# 3-CAN.net
KiCad netlist of a schematic drawn in Altium Designer
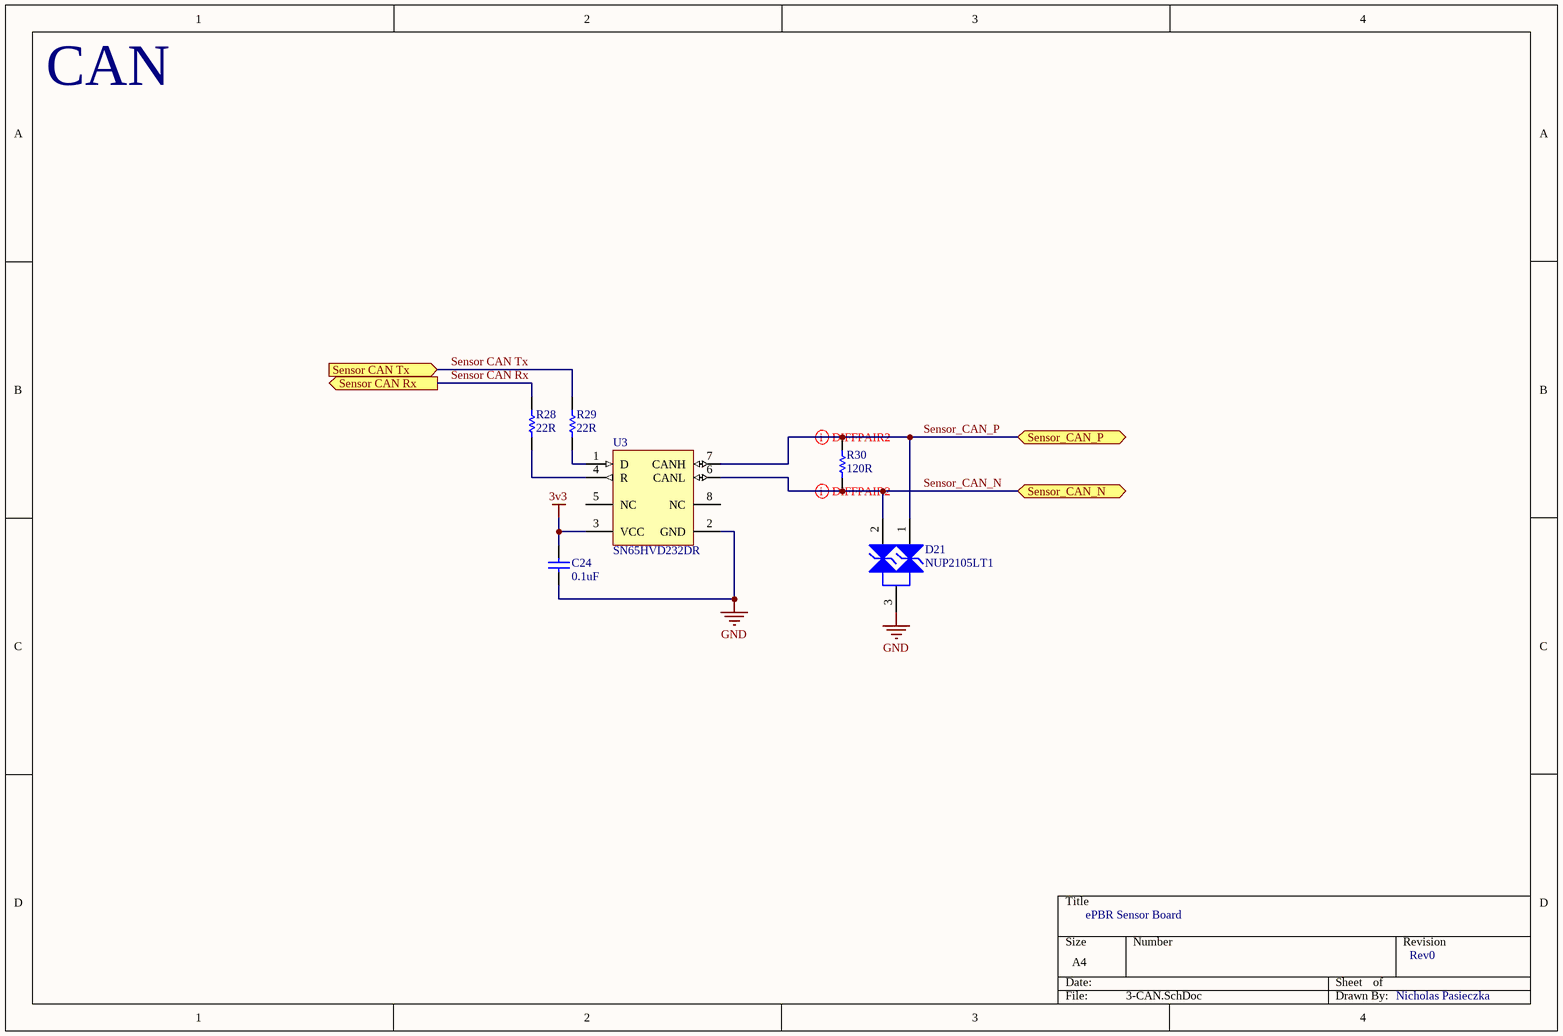
[diagram p0: 3-CAN.SchDoc]

(export (version "E")
  (design (tool "Eeschema 10.0.6"))
  (components
    (comp (ref "C24")
      (value "0.1uF")
      (footprint "CAPC1608X90X30NL10T20")
      (description "Chip Capacitor, 100 nF, +/- 10%, 50 V, -55 to 125 degC, 0603 (1608 Metric), RoHS, Tape and Reel")
      (fields (field (name "VOLTAGE") "50Vdc") (field (name "MANUFACTURER") "SamsungElectro-Mechanics"))
      (libsource (lib "Altium Content Vault") (part "CAP-NP-2"))
    )
    (comp (ref "D21")
      (value "NUP2105LT1")
      (footprint "ONSC-SOT-23-3-318-08_V")
      (description "Dual Line CAN Bus Protector, 3-Pin SOT-23, Tape and Reel")
      (fields (field (name "MANUFACTURER") "On Semiconductor"))
      (libsource (lib "Altium Content Vault") (part "ONSC-NUP21X5X-SOT-23-3-318-08"))
    )
    (comp (ref "R28")
      (value "22R")
      (footprint "RESC0603(1608)_N")
      (description "22R 0.1W 5% 0603 (1608 Metric)  SMD")
      (fields (field (name "POWER") "0.1 W") (field (name "TOLERANCE") "5 %"))
      (libsource (lib "Altium Content Vault") (part "RES"))
    )
    (comp (ref "R29")
      (value "22R")
      (footprint "RESC0603(1608)_N")
      (description "22R 0.1W 5% 0603 (1608 Metric)  SMD")
      (fields (field (name "POWER") "0.1 W") (field (name "TOLERANCE") "5 %"))
      (libsource (lib "Altium Content Vault") (part "RES"))
    )
    (comp (ref "R30")
      (value "120R")
      (footprint "RESC0603(1608)_N")
      (description "120R 0.1W 5% 0603 (1608 Metric)  SMD")
      (fields (field (name "POWER") "0.1 W") (field (name "TOLERANCE") "5 %"))
      (libsource (lib "Altium Content Vault") (part "RES"))
    )
    (comp (ref "U3")
      (value "SN65HVD232DR")
      (footprint "D0008A_M")
      (description "3.3 V Can Transceiver, 17 mA, -40 to 85 degC, 8-pin SOIC (D), Green (RoHS & no Sb/Br)")
      (fields (field (name "MANUFACTURER") "Texas Instruments"))
      (libsource (lib "Altium Content Vault") (part "TI-SN65HVD232-SOIC_D-8"))
    )
  )
  (nets
    (net (code "1") (name "/Sensor CAN Rx") (class "Default")
      (node (ref "R28") (pin "2") (pinfunction "2_2") (pintype "passive"))
    )
    (net (code "2") (name "/Sensor CAN Tx") (class "Default")
      (node (ref "R29") (pin "2") (pinfunction "2_2") (pintype "passive"))
    )
    (net (code "3") (name "/Sensor_CAN_N") (class "Default")
      (node (ref "D21") (pin "2") (pinfunction "K_2") (pintype "passive"))
      (node (ref "R30") (pin "1") (pinfunction "1_1") (pintype "passive"))
      (node (ref "U3") (pin "6") (pinfunction "CANL_6") (pintype "bidirectional"))
    )
    (net (code "4") (name "/Sensor_CAN_P") (class "Default")
      (node (ref "D21") (pin "1") (pinfunction "K_1") (pintype "passive"))
      (node (ref "R30") (pin "2") (pinfunction "2_2") (pintype "passive"))
      (node (ref "U3") (pin "7") (pinfunction "CANH_7") (pintype "bidirectional"))
    )
    (net (code "5") (name "3v3") (class "Default")
      (node (ref "C24") (pin "2") (pinfunction "2_2") (pintype "passive"))
      (node (ref "U3") (pin "3") (pinfunction "VCC_3") (pintype "power_in"))
    )
    (net (code "6") (name "GND") (class "Default")
      (node (ref "C24") (pin "1") (pinfunction "1_1") (pintype "passive"))
      (node (ref "D21") (pin "3") (pinfunction "K_3") (pintype "passive"))
      (node (ref "U3") (pin "2") (pinfunction "GND_2") (pintype "power_in"))
    )
    (net (code "7") (name "Net-(U3-D)") (class "Default")
      (node (ref "R29") (pin "1") (pinfunction "1_1") (pintype "passive"))
      (node (ref "U3") (pin "1") (pinfunction "D_1") (pintype "input"))
    )
    (net (code "8") (name "Net-(U3-R)") (class "Default")
      (node (ref "R28") (pin "1") (pinfunction "1_1") (pintype "passive"))
      (node (ref "U3") (pin "4") (pinfunction "R_4") (pintype "output"))
    )
    (net (code "9") (name "unconnected-(U3-NC-Pad5)") (class "Default")
      (node (ref "U3") (pin "5") (pinfunction "NC_5") (pintype "passive"))
    )
    (net (code "10") (name "unconnected-(U3-NC-Pad8)") (class "Default")
      (node (ref "U3") (pin "8") (pinfunction "NC_8") (pintype "passive"))
    )
  )
)
